# Fan_driver.net
KiCad netlist of a schematic drawn in Altium Designer
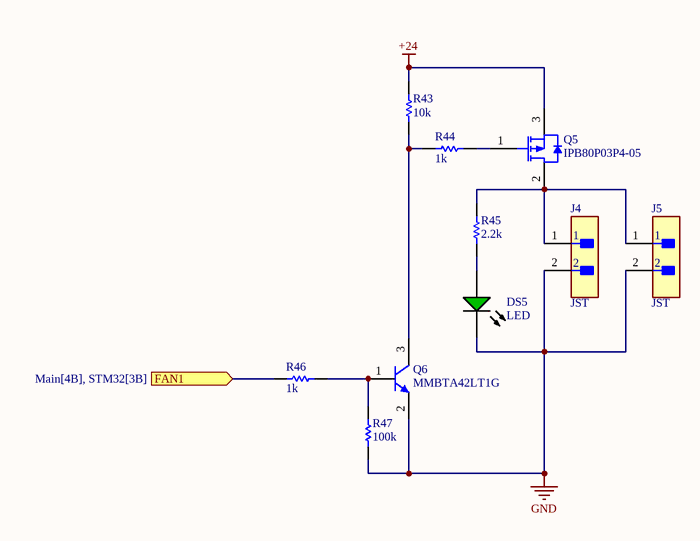
[diagram p0: Fan_driver.SchDoc]

(export (version "E")
  (design (tool "Eeschema 10.0.6"))
  (components
    (comp (ref "DS5")
      (value "LED")
      (footprint "AVAG-HSMX-C170_V")
      (description "Chip LED, Green, 2.2 V, -40 to 85 degC, 2-Pin SMD, Pb-Free, Tape and Reel")
      (fields (field (name "MANUFACTURER") "Avago"))
      (libsource (lib "Altium Content Vault") (part "LED_GREEN_A1K2-2"))
    )
    (comp (ref "J4")
      (value "JST")
      (footprint "FP-B2B-EH-A_LF_SN-MFG")
      (description "CONN HEADER VERT 2POS 2.5MM")
      (libsource (lib "Altium Content Vault") (part "3bc925449376181038e59eaffc5286c"))
    )
    (comp (ref "J5")
      (value "JST")
      (footprint "FP-B2B-EH-A_LF_SN-MFG")
      (description "CONN HEADER VERT 2POS 2.5MM")
      (libsource (lib "Altium Content Vault") (part "3bc925449376181038e59eaffc5286c"))
    )
    (comp (ref "Q5")
      (value "IPB80P03P4-05")
      (footprint "INF-PG-TO263-3-2_N")
      (description "OptiMOS-P2 Power-Transistor, -30 V VDS, -80 A ID, PG-TO263-3-2, Reel, Green")
      (fields (field (name "MANUFACTURER") "Infineon"))
      (libsource (lib "Altium Content Vault") (part "INF-MOSFET-P-3"))
    )
    (comp (ref "Q6")
      (value "MMBTA42LT1G")
      (footprint "ONSC-SOT-23-3-318-08_V")
      (description "High Voltage Transistor, NPN Silicon, 3-Pin SOT-23, Pb-Free, Tape and Reel")
      (fields (field (name "MANUFACTURER") "On Semiconductor"))
      (libsource (lib "Altium Content Vault") (part "ONSC-NPN-B1E2C3-3"))
    )
    (comp (ref "R43")
      (value "10k")
      (footprint "RESC2013X50X30LL20T20")
      (fields (field (name "MANUFACTURER") "Vishay Dale") (field (name "PART NUMBER") "CRCW08050000Z0EA"))
      (libsource (lib "Altium Content Vault") (part "RES"))
    )
    (comp (ref "R44")
      (value "1k")
      (footprint "RESC2013X50X30LL20T20")
      (fields (field (name "MANUFACTURER") "Vishay Dale") (field (name "PART NUMBER") "CRCW08050000Z0EA"))
      (libsource (lib "Altium Content Vault") (part "RES"))
    )
    (comp (ref "R45")
      (value "2.2k")
      (footprint "RESC2013X50X30LL20T20")
      (fields (field (name "MANUFACTURER") "Vishay Dale") (field (name "PART NUMBER") "CRCW08050000Z0EA"))
      (libsource (lib "Altium Content Vault") (part "RES"))
    )
    (comp (ref "R46")
      (value "1k")
      (footprint "RESC2013X50X30LL20T20")
      (fields (field (name "MANUFACTURER") "Vishay Dale") (field (name "PART NUMBER") "CRCW08050000Z0EA"))
      (libsource (lib "Altium Content Vault") (part "RES"))
    )
    (comp (ref "R47")
      (value "100k")
      (footprint "RESC2013X50X30LL20T20")
      (fields (field (name "MANUFACTURER") "Vishay Dale") (field (name "PART NUMBER") "CRCW08050000Z0EA"))
      (libsource (lib "Altium Content Vault") (part "RES"))
    )
  )
  (nets
    (net (code "1") (name "+24") (class "Default")
      (node (ref "Q5") (pin "3") (pinfunction "SOURCE_3") (pintype "passive"))
      (node (ref "R43") (pin "2") (pinfunction "2_2") (pintype "passive"))
    )
    (net (code "2") (name "/FAN1") (class "Default")
      (node (ref "R46") (pin "1") (pinfunction "1_1") (pintype "passive"))
    )
    (net (code "3") (name "GND") (class "Default")
      (node (ref "DS5") (pin "2") (pinfunction "K_2") (pintype "passive"))
      (node (ref "J4") (pin "2") (pinfunction "2_2") (pintype "passive"))
      (node (ref "J5") (pin "2") (pinfunction "2_2") (pintype "passive"))
      (node (ref "Q6") (pin "2") (pinfunction "E_2") (pintype "passive"))
      (node (ref "R47") (pin "1") (pinfunction "1_1") (pintype "passive"))
    )
    (net (code "4") (name "Net-(DS5-A)") (class "Default")
      (node (ref "DS5") (pin "1") (pinfunction "A_1") (pintype "passive"))
      (node (ref "R45") (pin "1") (pinfunction "1_1") (pintype "passive"))
    )
    (net (code "5") (name "Net-(Q5-DRAIN)") (class "Default")
      (node (ref "J4") (pin "1") (pinfunction "1_1") (pintype "passive"))
      (node (ref "J5") (pin "1") (pinfunction "1_1") (pintype "passive"))
      (node (ref "Q5") (pin "2") (pinfunction "DRAIN_2") (pintype "passive"))
      (node (ref "R45") (pin "2") (pinfunction "2_2") (pintype "passive"))
    )
    (net (code "6") (name "Net-(Q5-GATE)") (class "Default")
      (node (ref "Q5") (pin "1") (pinfunction "GATE_1") (pintype "passive"))
      (node (ref "R44") (pin "2") (pinfunction "2_2") (pintype "passive"))
    )
    (net (code "7") (name "Net-(Q6-B)") (class "Default")
      (node (ref "Q6") (pin "1") (pinfunction "B_1") (pintype "passive"))
      (node (ref "R46") (pin "2") (pinfunction "2_2") (pintype "passive"))
      (node (ref "R47") (pin "2") (pinfunction "2_2") (pintype "passive"))
    )
    (net (code "8") (name "Net-(Q6-C)") (class "Default")
      (node (ref "Q6") (pin "3") (pinfunction "C_3") (pintype "passive"))
      (node (ref "R43") (pin "1") (pinfunction "1_1") (pintype "passive"))
      (node (ref "R44") (pin "1") (pinfunction "1_1") (pintype "passive"))
    )
  )
)
